# MCP73837_LiPo_Charger.net
KiCad netlist of a schematic drawn in EAGLE
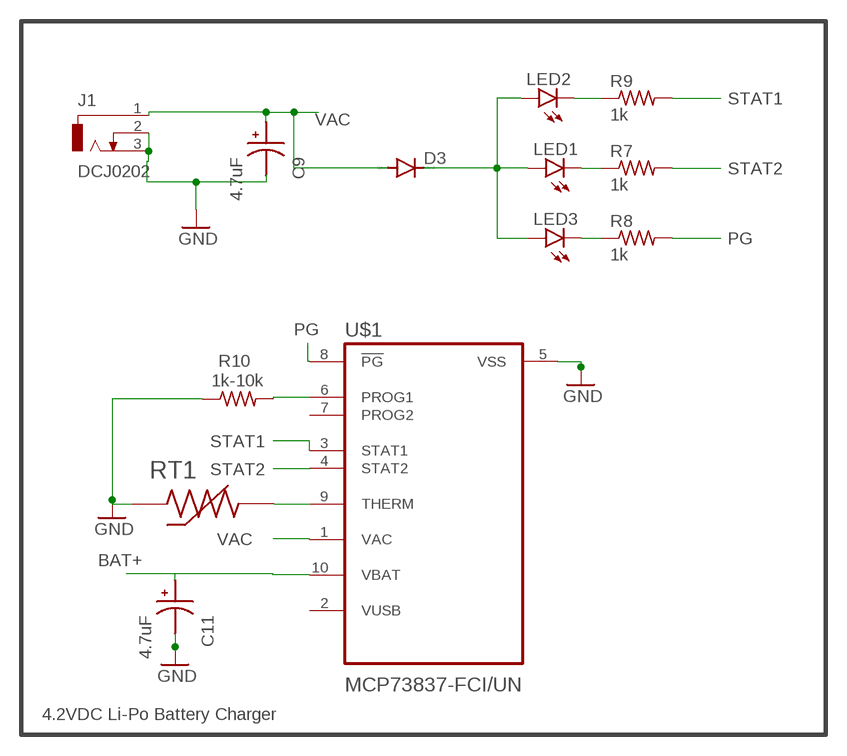
[diagram p0: schematic, sheet 1]

(export (version "E")
  (design (tool "Eeschema 10.0.6"))
  (components
    (comp (ref "C9")
      (value "4.7uF")
      (footprint "eagle-import:CAPAE430X550N")
      (fields (field (name "MF") "Panasonic") (field (name "MP") "EEE-1CA100SR"))
      (libsource (lib "eagle-import") (part "EEE-1CA100SR"))
    )
    (comp (ref "C11")
      (value "4.7uF")
      (footprint "eagle-import:CAPAE430X550N")
      (fields (field (name "MF") "Panasonic") (field (name "MP") "EEE-1CA100SR"))
      (libsource (lib "eagle-import") (part "EEE-1CA100SR"))
    )
    (comp (ref "D3")
      (value "DIODE-DO214BA")
      (footprint "eagle-import:DO214BA")
      (libsource (lib "eagle-import") (part "DIODE-DO214BA"))
    )
    (comp (ref "J1")
      (value "DCJ0202")
      (footprint "eagle-import:DCJ0202")
      (libsource (lib "eagle-import") (part "DCJ0202"))
    )
    (comp (ref "LED1")
      (value "LEDCHIP-LED0805")
      (footprint "eagle-import:CHIP-LED0805")
      (libsource (lib "eagle-import") (part "LEDCHIP-LED0805"))
    )
    (comp (ref "LED2")
      (value "LEDCHIP-LED0805")
      (footprint "eagle-import:CHIP-LED0805")
      (libsource (lib "eagle-import") (part "LEDCHIP-LED0805"))
    )
    (comp (ref "LED3")
      (value "LEDCHIP-LED0805")
      (footprint "eagle-import:CHIP-LED0805")
      (libsource (lib "eagle-import") (part "LEDCHIP-LED0805"))
    )
    (comp (ref "R7")
      (value "1k")
      (footprint "eagle-import:RESC2012X65N")
      (fields (field (name "MF") "TE Connectivity") (field (name "MP") "RP73PF2A10KBTDF"))
      (libsource (lib "eagle-import") (part "RP73PF2A10KBTDF"))
    )
    (comp (ref "R8")
      (value "1k")
      (footprint "eagle-import:RESC2012X65N")
      (fields (field (name "MF") "TE Connectivity") (field (name "MP") "RP73PF2A10KBTDF"))
      (libsource (lib "eagle-import") (part "RP73PF2A10KBTDF"))
    )
    (comp (ref "R9")
      (value "1k")
      (footprint "eagle-import:RESC2012X65N")
      (fields (field (name "MF") "TE Connectivity") (field (name "MP") "RP73PF2A10KBTDF"))
      (libsource (lib "eagle-import") (part "RP73PF2A10KBTDF"))
    )
    (comp (ref "R10")
      (value "1k-10k")
      (footprint "eagle-import:RESC2012X65N")
      (fields (field (name "MF") "TE Connectivity") (field (name "MP") "RP73PF2A10KBTDF"))
      (libsource (lib "eagle-import") (part "RP73PF2A10KBTDF"))
    )
    (comp (ref "RT1")
      (value "NCP18XW223E03RB")
      (footprint "eagle-import:THRMC1608X95N")
      (fields (field (name "MF") "Murata"))
      (libsource (lib "eagle-import") (part "NCP18XW223E03RB"))
    )
    (comp (ref "U$1")
      (value "MCP73837-FCI/UN")
      (footprint "eagle-import:SOP50P490X110-10N")
      (fields (field (name "MF") "Microchip"))
      (libsource (lib "eagle-import") (part "MCP73837-FCI/UN"))
    )
  )
  (nets
    (net (code "1") (name "/BAT+") (class "Default")
      (node (ref "C11") (pin "1") (pinfunction "1_1") (pintype "passive"))
      (node (ref "U$1") (pin "10") (pinfunction "VBAT_10") (pintype "bidirectional"))
    )
    (net (code "2") (name "/PG") (class "Default")
      (node (ref "R8") (pin "2") (pinfunction "2_2") (pintype "passive"))
      (node (ref "U$1") (pin "8") (pinfunction "~{PG}_8") (pintype "bidirectional"))
    )
    (net (code "3") (name "/STAT1") (class "Default")
      (node (ref "R9") (pin "2") (pinfunction "2_2") (pintype "passive"))
      (node (ref "U$1") (pin "3") (pinfunction "STAT1_3") (pintype "bidirectional"))
    )
    (net (code "4") (name "/STAT2") (class "Default")
      (node (ref "R7") (pin "2") (pinfunction "2_2") (pintype "passive"))
      (node (ref "U$1") (pin "4") (pinfunction "STAT2_4") (pintype "bidirectional"))
    )
    (net (code "5") (name "/VAC") (class "Default")
      (node (ref "C9") (pin "1") (pinfunction "1_1") (pintype "passive"))
      (node (ref "D3") (pin "A") (pinfunction "A_A") (pintype "passive"))
      (node (ref "J1") (pin "1") (pinfunction "1_1") (pintype "passive"))
      (node (ref "U$1") (pin "1") (pinfunction "VAC_1") (pintype "bidirectional"))
    )
    (net (code "6") (name "GND") (class "Default")
      (node (ref "C11") (pin "2") (pinfunction "2_2") (pintype "passive"))
      (node (ref "C9") (pin "2") (pinfunction "2_2") (pintype "passive"))
      (node (ref "J1") (pin "2") (pinfunction "2_2") (pintype "passive"))
      (node (ref "J1") (pin "3") (pinfunction "3_3") (pintype "passive"))
      (node (ref "R10") (pin "1") (pinfunction "1_1") (pintype "passive"))
      (node (ref "RT1") (pin "1") (pinfunction "1_1") (pintype "passive"))
      (node (ref "U$1") (pin "5") (pinfunction "VSS_5") (pintype "power_in"))
    )
    (net (code "7") (name "Net-(D3-PadC)") (class "Default")
      (node (ref "D3") (pin "C") (pinfunction "C_C") (pintype "passive"))
      (node (ref "LED1") (pin "A") (pinfunction "A_A") (pintype "passive"))
      (node (ref "LED2") (pin "A") (pinfunction "A_A") (pintype "passive"))
      (node (ref "LED3") (pin "A") (pinfunction "A_A") (pintype "passive"))
    )
    (net (code "8") (name "Net-(LED1-PadC)") (class "Default")
      (node (ref "LED1") (pin "C") (pinfunction "C_C") (pintype "passive"))
      (node (ref "R7") (pin "1") (pinfunction "1_1") (pintype "passive"))
    )
    (net (code "9") (name "Net-(LED2-PadC)") (class "Default")
      (node (ref "LED2") (pin "C") (pinfunction "C_C") (pintype "passive"))
      (node (ref "R9") (pin "1") (pinfunction "1_1") (pintype "passive"))
    )
    (net (code "10") (name "Net-(LED3-PadC)") (class "Default")
      (node (ref "LED3") (pin "C") (pinfunction "C_C") (pintype "passive"))
      (node (ref "R8") (pin "1") (pinfunction "1_1") (pintype "passive"))
    )
    (net (code "11") (name "Net-(U$1-PROG1)") (class "Default")
      (node (ref "R10") (pin "2") (pinfunction "2_2") (pintype "passive"))
      (node (ref "U$1") (pin "6") (pinfunction "PROG1_6") (pintype "bidirectional"))
    )
    (net (code "12") (name "Net-(U$1-THERM)") (class "Default")
      (node (ref "RT1") (pin "2") (pinfunction "2_2") (pintype "passive"))
      (node (ref "U$1") (pin "9") (pinfunction "THERM_9") (pintype "bidirectional"))
    )
    (net (code "13") (name "unconnected-(U$1-PROG2-Pad7)") (class "Default")
      (node (ref "U$1") (pin "7") (pinfunction "PROG2_7") (pintype "bidirectional"))
    )
    (net (code "14") (name "unconnected-(U$1-VUSB-Pad2)") (class "Default")
      (node (ref "U$1") (pin "2") (pinfunction "VUSB_2") (pintype "bidirectional"))
    )
  )
)
